# final_manual.net
KiCad netlist of a schematic drawn in EAGLE
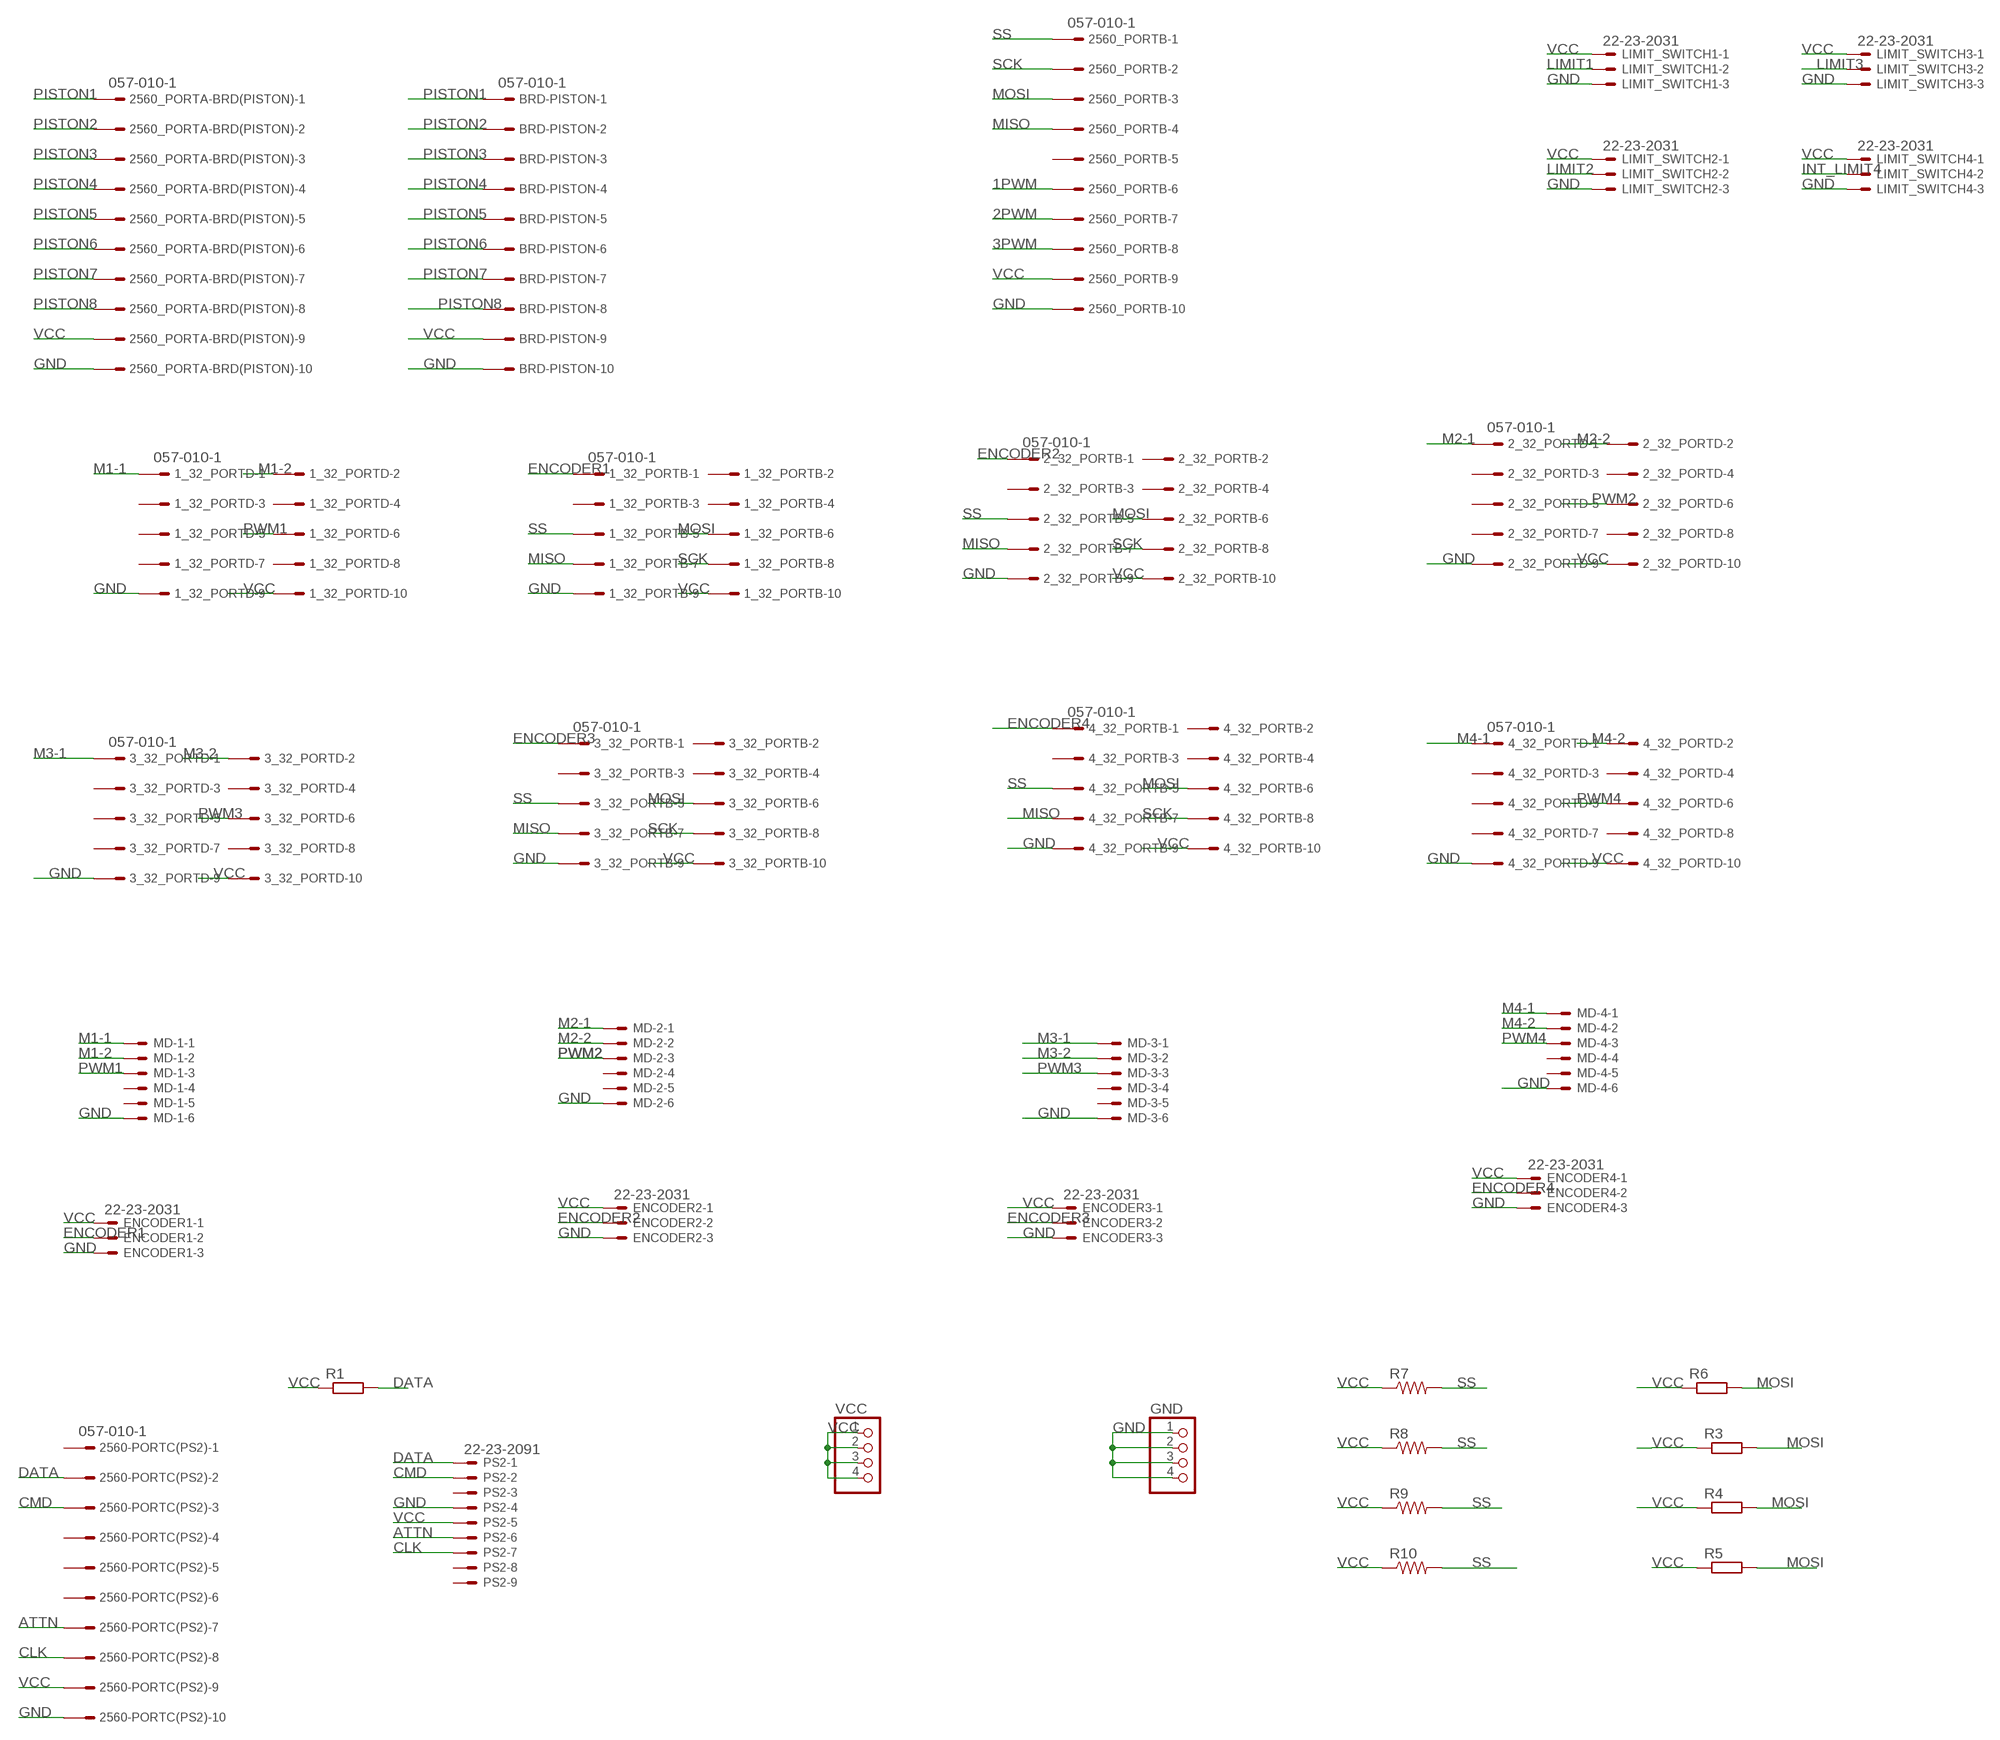
[diagram p0: schematic, sheet 1, part 1 of 2]
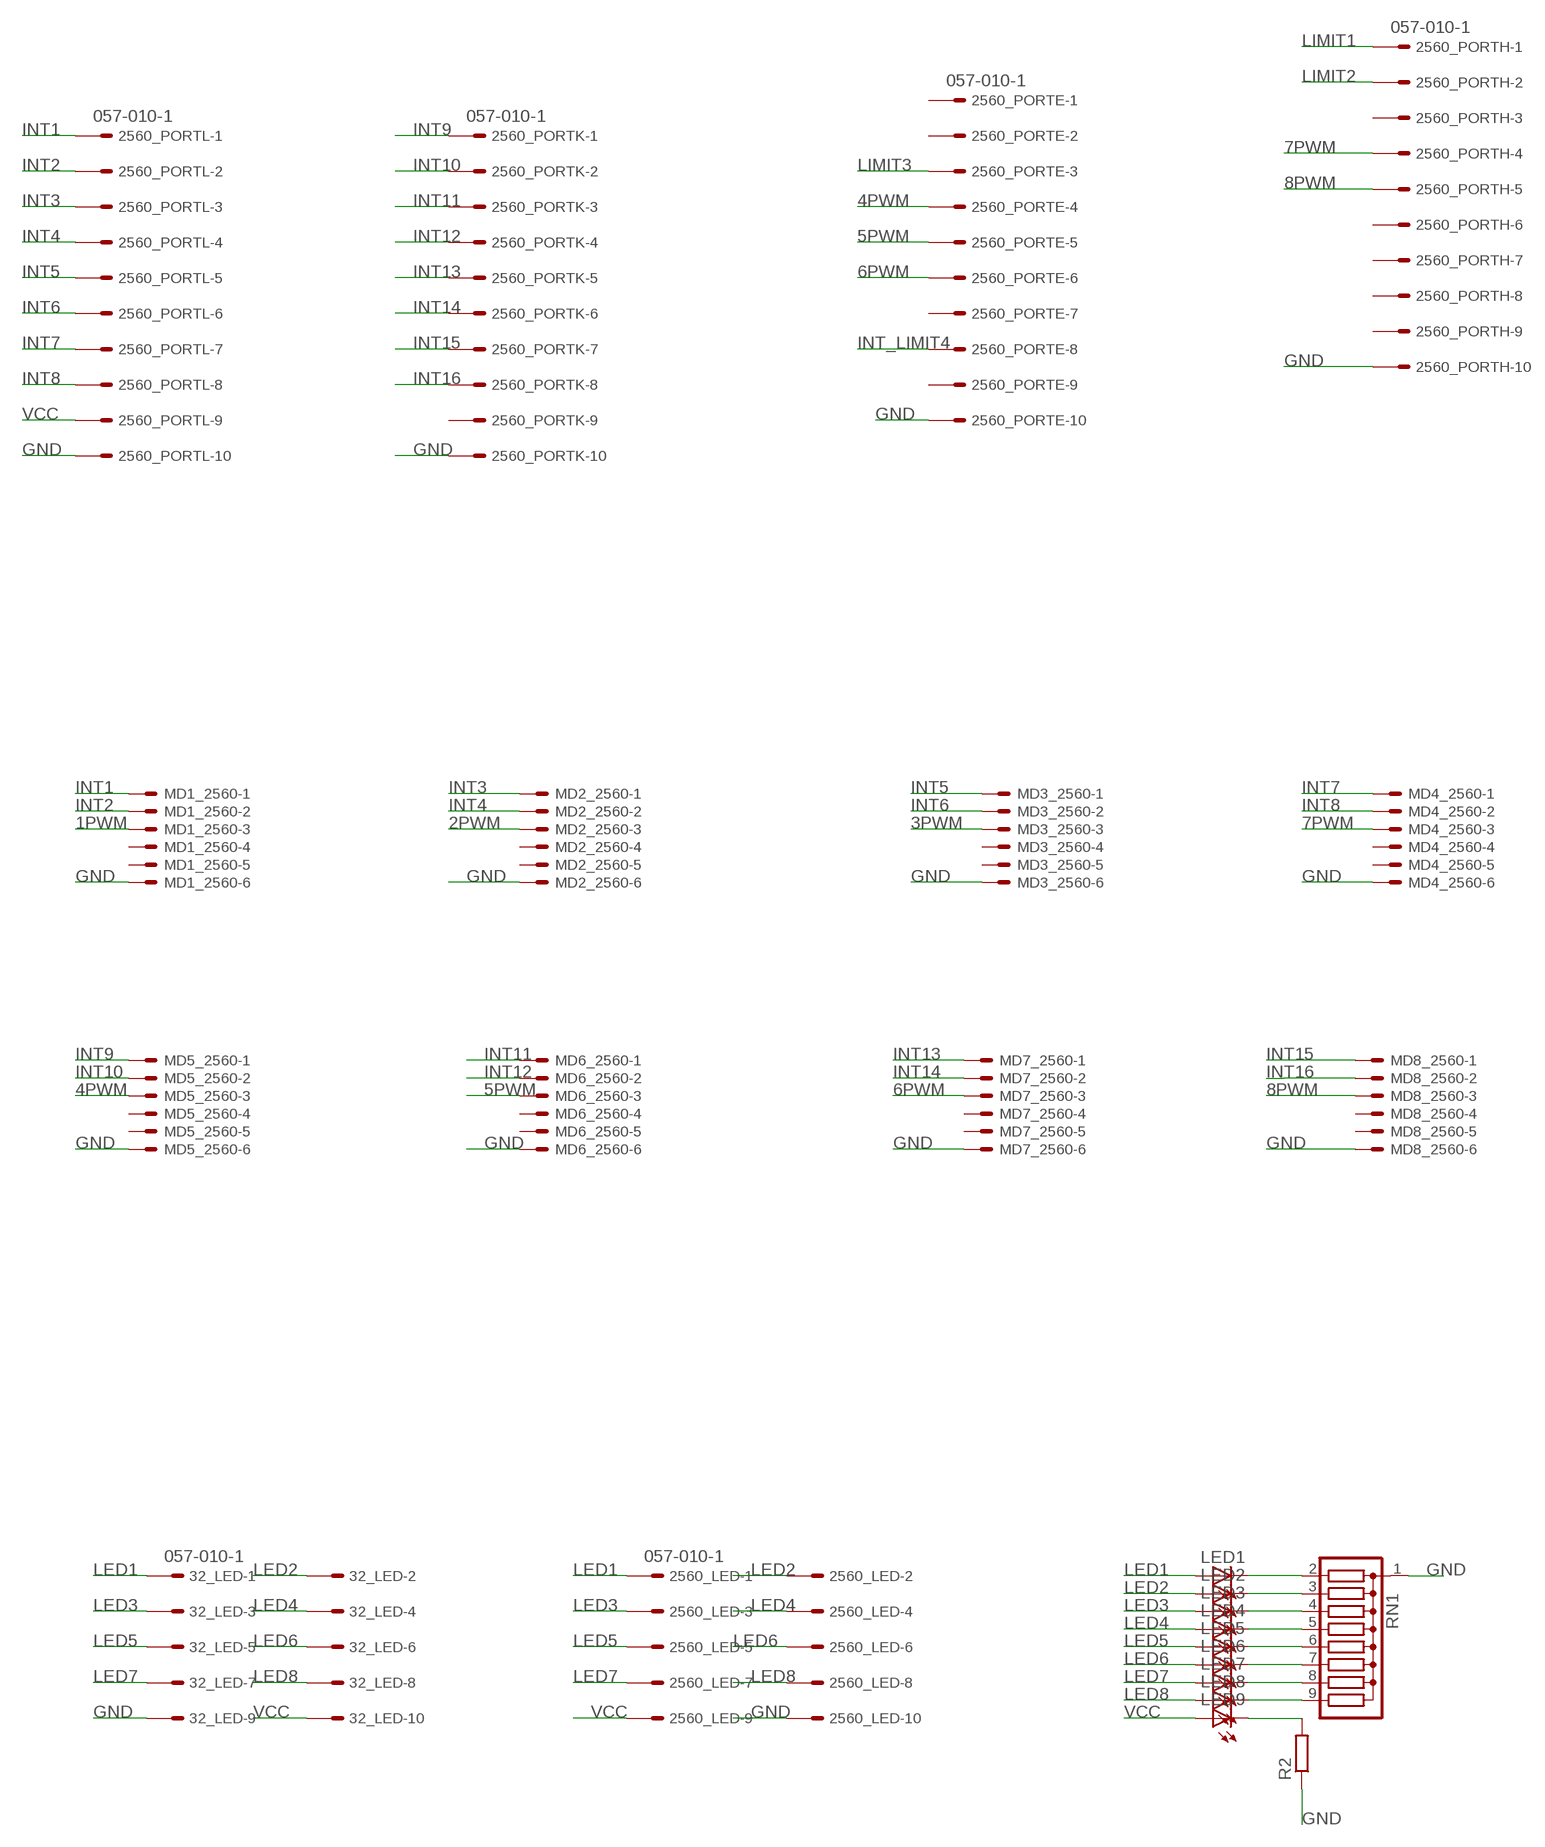
[diagram p1: schematic, sheet 1, part 2 of 2]

(export (version "E")
  (design (tool "Eeschema 10.0.6"))
  (components
    (comp (ref "1_32_PORTB")
      (value "057-010-1")
      (footprint "eagle-import:057-010-1")
      (libsource (lib "eagle-import") (part "057-010-1"))
    )
    (comp (ref "1_32_PORTD")
      (value "057-010-1")
      (footprint "eagle-import:057-010-1")
      (libsource (lib "eagle-import") (part "057-010-1"))
    )
    (comp (ref "2_32_PORTB")
      (value "057-010-1")
      (footprint "eagle-import:057-010-1")
      (libsource (lib "eagle-import") (part "057-010-1"))
    )
    (comp (ref "2_32_PORTD")
      (value "057-010-1")
      (footprint "eagle-import:057-010-1")
      (libsource (lib "eagle-import") (part "057-010-1"))
    )
    (comp (ref "3_32_PORTB")
      (value "057-010-1")
      (footprint "eagle-import:057-010-1")
      (libsource (lib "eagle-import") (part "057-010-1"))
    )
    (comp (ref "3_32_PORTD")
      (value "057-010-1")
      (footprint "eagle-import:057-010-1")
      (libsource (lib "eagle-import") (part "057-010-1"))
    )
    (comp (ref "4_32_PORTB")
      (value "057-010-1")
      (footprint "eagle-import:057-010-1")
      (libsource (lib "eagle-import") (part "057-010-1"))
    )
    (comp (ref "4_32_PORTD")
      (value "057-010-1")
      (footprint "eagle-import:057-010-1")
      (libsource (lib "eagle-import") (part "057-010-1"))
    )
    (comp (ref "32_LED")
      (value "057-010-1")
      (footprint "eagle-import:057-010-1")
      (libsource (lib "eagle-import") (part "057-010-1"))
    )
    (comp (ref "2560-PORTC(PS2)")
      (value "057-010-1")
      (footprint "eagle-import:057-010-1")
      (libsource (lib "eagle-import") (part "057-010-1"))
    )
    (comp (ref "2560_LED")
      (value "057-010-1")
      (footprint "eagle-import:057-010-1")
      (libsource (lib "eagle-import") (part "057-010-1"))
    )
    (comp (ref "2560_PORTA-BRD(PISTON)")
      (value "057-010-1")
      (footprint "eagle-import:057-010-1")
      (libsource (lib "eagle-import") (part "057-010-1"))
    )
    (comp (ref "2560_PORTB")
      (value "057-010-1")
      (footprint "eagle-import:057-010-1")
      (libsource (lib "eagle-import") (part "057-010-1"))
    )
    (comp (ref "2560_PORTE")
      (value "057-010-1")
      (footprint "eagle-import:057-010-1")
      (libsource (lib "eagle-import") (part "057-010-1"))
    )
    (comp (ref "2560_PORTH")
      (value "057-010-1")
      (footprint "eagle-import:057-010-1")
      (libsource (lib "eagle-import") (part "057-010-1"))
    )
    (comp (ref "2560_PORTK")
      (value "057-010-1")
      (footprint "eagle-import:057-010-1")
      (libsource (lib "eagle-import") (part "057-010-1"))
    )
    (comp (ref "2560_PORTL")
      (value "057-010-1")
      (footprint "eagle-import:057-010-1")
      (libsource (lib "eagle-import") (part "057-010-1"))
    )
    (comp (ref "BRD-PISTON")
      (value "057-010-1")
      (footprint "eagle-import:057-010-1")
      (libsource (lib "eagle-import") (part "057-010-1"))
    )
    (comp (ref "ENCODER1")
      (value "22-23-2031")
      (footprint "eagle-import:22-23-2031")
      (fields (field (name "MF") "MOLEX"))
      (libsource (lib "eagle-import") (part "22-23-2031"))
    )
    (comp (ref "ENCODER2")
      (value "22-23-2031")
      (footprint "eagle-import:22-23-2031")
      (fields (field (name "MF") "MOLEX"))
      (libsource (lib "eagle-import") (part "22-23-2031"))
    )
    (comp (ref "ENCODER3")
      (value "22-23-2031")
      (footprint "eagle-import:22-23-2031")
      (fields (field (name "MF") "MOLEX"))
      (libsource (lib "eagle-import") (part "22-23-2031"))
    )
    (comp (ref "ENCODER4")
      (value "22-23-2031")
      (footprint "eagle-import:22-23-2031")
      (fields (field (name "MF") "MOLEX"))
      (libsource (lib "eagle-import") (part "22-23-2031"))
    )
    (comp (ref "GND")
      (value "PINHD-1X4")
      (footprint "eagle-import:1X04")
      (libsource (lib "eagle-import") (part "PINHD-1X4"))
    )
    (comp (ref "LED1")
      (value "LED3MM")
      (footprint "eagle-import:LED3MM")
      (libsource (lib "eagle-import") (part "LED3MM"))
    )
    (comp (ref "LED2")
      (value "LED3MM")
      (footprint "eagle-import:LED3MM")
      (libsource (lib "eagle-import") (part "LED3MM"))
    )
    (comp (ref "LED3")
      (value "LED3MM")
      (footprint "eagle-import:LED3MM")
      (libsource (lib "eagle-import") (part "LED3MM"))
    )
    (comp (ref "LED4")
      (value "LED3MM")
      (footprint "eagle-import:LED3MM")
      (libsource (lib "eagle-import") (part "LED3MM"))
    )
    (comp (ref "LED5")
      (value "LED3MM")
      (footprint "eagle-import:LED3MM")
      (libsource (lib "eagle-import") (part "LED3MM"))
    )
    (comp (ref "LED6")
      (value "LED3MM")
      (footprint "eagle-import:LED3MM")
      (libsource (lib "eagle-import") (part "LED3MM"))
    )
    (comp (ref "LED7")
      (value "LED3MM")
      (footprint "eagle-import:LED3MM")
      (libsource (lib "eagle-import") (part "LED3MM"))
    )
    (comp (ref "LED8")
      (value "LED3MM")
      (footprint "eagle-import:LED3MM")
      (libsource (lib "eagle-import") (part "LED3MM"))
    )
    (comp (ref "LED9")
      (value "LED3MM")
      (footprint "eagle-import:LED3MM")
      (libsource (lib "eagle-import") (part "LED3MM"))
    )
    (comp (ref "LIMIT_SWITCH1")
      (value "22-23-2031")
      (footprint "eagle-import:22-23-2031")
      (fields (field (name "MF") "MOLEX"))
      (libsource (lib "eagle-import") (part "22-23-2031"))
    )
    (comp (ref "LIMIT_SWITCH2")
      (value "22-23-2031")
      (footprint "eagle-import:22-23-2031")
      (fields (field (name "MF") "MOLEX"))
      (libsource (lib "eagle-import") (part "22-23-2031"))
    )
    (comp (ref "LIMIT_SWITCH3")
      (value "22-23-2031")
      (footprint "eagle-import:22-23-2031")
      (fields (field (name "MF") "MOLEX"))
      (libsource (lib "eagle-import") (part "22-23-2031"))
    )
    (comp (ref "LIMIT_SWITCH4")
      (value "22-23-2031")
      (footprint "eagle-import:22-23-2031")
      (fields (field (name "MF") "MOLEX"))
      (libsource (lib "eagle-import") (part "22-23-2031"))
    )
    (comp (ref "MD-1")
      (value "22-23-2061")
      (footprint "eagle-import:22-23-2061")
      (fields (field (name "MF") "MOLEX"))
      (libsource (lib "eagle-import") (part "22-23-2061"))
    )
    (comp (ref "MD-2")
      (value "22-23-2061")
      (footprint "eagle-import:22-23-2061")
      (fields (field (name "MF") "MOLEX"))
      (libsource (lib "eagle-import") (part "22-23-2061"))
    )
    (comp (ref "MD-3")
      (value "22-23-2061")
      (footprint "eagle-import:22-23-2061")
      (fields (field (name "MF") "MOLEX"))
      (libsource (lib "eagle-import") (part "22-23-2061"))
    )
    (comp (ref "MD-4")
      (value "22-23-2061")
      (footprint "eagle-import:22-23-2061")
      (fields (field (name "MF") "MOLEX"))
      (libsource (lib "eagle-import") (part "22-23-2061"))
    )
    (comp (ref "MD1_2560")
      (value "22-23-2061")
      (footprint "eagle-import:22-23-2061")
      (fields (field (name "MF") "MOLEX"))
      (libsource (lib "eagle-import") (part "22-23-2061"))
    )
    (comp (ref "MD2_2560")
      (value "22-23-2061")
      (footprint "eagle-import:22-23-2061")
      (fields (field (name "MF") "MOLEX"))
      (libsource (lib "eagle-import") (part "22-23-2061"))
    )
    (comp (ref "MD3_2560")
      (value "22-23-2061")
      (footprint "eagle-import:22-23-2061")
      (fields (field (name "MF") "MOLEX"))
      (libsource (lib "eagle-import") (part "22-23-2061"))
    )
    (comp (ref "MD4_2560")
      (value "22-23-2061")
      (footprint "eagle-import:22-23-2061")
      (fields (field (name "MF") "MOLEX"))
      (libsource (lib "eagle-import") (part "22-23-2061"))
    )
    (comp (ref "MD5_2560")
      (value "22-23-2061")
      (footprint "eagle-import:22-23-2061")
      (fields (field (name "MF") "MOLEX"))
      (libsource (lib "eagle-import") (part "22-23-2061"))
    )
    (comp (ref "MD6_2560")
      (value "22-23-2061")
      (footprint "eagle-import:22-23-2061")
      (fields (field (name "MF") "MOLEX"))
      (libsource (lib "eagle-import") (part "22-23-2061"))
    )
    (comp (ref "MD7_2560")
      (value "22-23-2061")
      (footprint "eagle-import:22-23-2061")
      (fields (field (name "MF") "MOLEX"))
      (libsource (lib "eagle-import") (part "22-23-2061"))
    )
    (comp (ref "MD8_2560")
      (value "22-23-2061")
      (footprint "eagle-import:22-23-2061")
      (fields (field (name "MF") "MOLEX"))
      (libsource (lib "eagle-import") (part "22-23-2061"))
    )
    (comp (ref "PS2")
      (value "22-23-2091")
      (footprint "eagle-import:22-23-2091")
      (fields (field (name "MF") "MOLEX"))
      (libsource (lib "eagle-import") (part "22-23-2091"))
    )
    (comp (ref "R1")
      (value "R-EU_0204/7")
      (footprint "eagle-import:0204_7")
      (libsource (lib "eagle-import") (part "R-EU_0204/7"))
    )
    (comp (ref "R2")
      (value "R-EU_0204/7")
      (footprint "eagle-import:0204_7")
      (libsource (lib "eagle-import") (part "R-EU_0204/7"))
    )
    (comp (ref "R3")
      (value "R-EU_0204/7")
      (footprint "eagle-import:0204_7")
      (libsource (lib "eagle-import") (part "R-EU_0204/7"))
    )
    (comp (ref "R4")
      (value "R-EU_0204/7")
      (footprint "eagle-import:0204_7")
      (libsource (lib "eagle-import") (part "R-EU_0204/7"))
    )
    (comp (ref "R5")
      (value "R-EU_0204/7")
      (footprint "eagle-import:0204_7")
      (libsource (lib "eagle-import") (part "R-EU_0204/7"))
    )
    (comp (ref "R6")
      (value "R-EU_0204/7")
      (footprint "eagle-import:0204_7")
      (libsource (lib "eagle-import") (part "R-EU_0204/7"))
    )
    (comp (ref "R7")
      (value "R-US_0204/7")
      (footprint "eagle-import:0204_7")
      (libsource (lib "eagle-import") (part "R-US_0204/7"))
    )
    (comp (ref "R8")
      (value "R-US_0204/7")
      (footprint "eagle-import:0204_7")
      (libsource (lib "eagle-import") (part "R-US_0204/7"))
    )
    (comp (ref "R9")
      (value "R-US_0204/7")
      (footprint "eagle-import:0204_7")
      (libsource (lib "eagle-import") (part "R-US_0204/7"))
    )
    (comp (ref "R10")
      (value "R-US_0204/7")
      (footprint "eagle-import:0204_7")
      (libsource (lib "eagle-import") (part "R-US_0204/7"))
    )
    (comp (ref "RN1")
      (value "G08R")
      (footprint "eagle-import:SIL9")
      (libsource (lib "eagle-import") (part "G08R"))
    )
    (comp (ref "VCC")
      (value "PINHD-1X4")
      (footprint "eagle-import:1X04")
      (libsource (lib "eagle-import") (part "PINHD-1X4"))
    )
  )
  (nets
    (net (code "1") (name "/1PWM") (class "Default")
      (node (ref "2560_PORTB") (pin "6") (pinfunction "S_6") (pintype "passive"))
      (node (ref "MD1_2560") (pin "3") (pinfunction "S_3") (pintype "passive"))
    )
    (net (code "2") (name "/2PWM") (class "Default")
      (node (ref "2560_PORTB") (pin "7") (pinfunction "S_7") (pintype "passive"))
      (node (ref "MD2_2560") (pin "3") (pinfunction "S_3") (pintype "passive"))
    )
    (net (code "3") (name "/3PWM") (class "Default")
      (node (ref "2560_PORTB") (pin "8") (pinfunction "S_8") (pintype "passive"))
      (node (ref "MD3_2560") (pin "3") (pinfunction "S_3") (pintype "passive"))
    )
    (net (code "4") (name "/4PWM") (class "Default")
      (node (ref "2560_PORTE") (pin "4") (pinfunction "S_4") (pintype "passive"))
      (node (ref "MD5_2560") (pin "3") (pinfunction "S_3") (pintype "passive"))
    )
    (net (code "5") (name "/5PWM") (class "Default")
      (node (ref "2560_PORTE") (pin "5") (pinfunction "S_5") (pintype "passive"))
      (node (ref "MD6_2560") (pin "3") (pinfunction "S_3") (pintype "passive"))
    )
    (net (code "6") (name "/6PWM") (class "Default")
      (node (ref "2560_PORTE") (pin "6") (pinfunction "S_6") (pintype "passive"))
      (node (ref "MD7_2560") (pin "3") (pinfunction "S_3") (pintype "passive"))
    )
    (net (code "7") (name "/7PWM") (class "Default")
      (node (ref "2560_PORTH") (pin "4") (pinfunction "S_4") (pintype "passive"))
      (node (ref "MD4_2560") (pin "3") (pinfunction "S_3") (pintype "passive"))
    )
    (net (code "8") (name "/8PWM") (class "Default")
      (node (ref "2560_PORTH") (pin "5") (pinfunction "S_5") (pintype "passive"))
      (node (ref "MD8_2560") (pin "3") (pinfunction "S_3") (pintype "passive"))
    )
    (net (code "9") (name "/ATTN") (class "Default")
      (node (ref "2560-PORTC(PS2)") (pin "7") (pinfunction "S_7") (pintype "passive"))
      (node (ref "PS2") (pin "6") (pinfunction "S_6") (pintype "passive"))
    )
    (net (code "10") (name "/CLK") (class "Default")
      (node (ref "2560-PORTC(PS2)") (pin "8") (pinfunction "S_8") (pintype "passive"))
      (node (ref "PS2") (pin "7") (pinfunction "S_7") (pintype "passive"))
    )
    (net (code "11") (name "/CMD") (class "Default")
      (node (ref "2560-PORTC(PS2)") (pin "3") (pinfunction "S_3") (pintype "passive"))
      (node (ref "PS2") (pin "2") (pinfunction "S_2") (pintype "passive"))
    )
    (net (code "12") (name "/DATA") (class "Default")
      (node (ref "2560-PORTC(PS2)") (pin "2") (pinfunction "S_2") (pintype "passive"))
      (node (ref "PS2") (pin "1") (pinfunction "S_1") (pintype "passive"))
      (node (ref "R1") (pin "2") (pinfunction "2_2") (pintype "passive"))
    )
    (net (code "13") (name "/ENCODER1") (class "Default")
      (node (ref "1_32_PORTB") (pin "1") (pinfunction "S_1") (pintype "passive"))
      (node (ref "ENCODER1") (pin "2") (pinfunction "S_2") (pintype "passive"))
    )
    (net (code "14") (name "/ENCODER2") (class "Default")
      (node (ref "2_32_PORTB") (pin "1") (pinfunction "S_1") (pintype "passive"))
      (node (ref "ENCODER2") (pin "2") (pinfunction "S_2") (pintype "passive"))
    )
    (net (code "15") (name "/ENCODER3") (class "Default")
      (node (ref "3_32_PORTB") (pin "1") (pinfunction "S_1") (pintype "passive"))
      (node (ref "ENCODER3") (pin "2") (pinfunction "S_2") (pintype "passive"))
    )
    (net (code "16") (name "/ENCODER4") (class "Default")
      (node (ref "4_32_PORTB") (pin "1") (pinfunction "S_1") (pintype "passive"))
      (node (ref "ENCODER4") (pin "2") (pinfunction "S_2") (pintype "passive"))
    )
    (net (code "17") (name "/GND") (class "Default")
      (node (ref "1_32_PORTB") (pin "9") (pinfunction "S_9") (pintype "passive"))
      (node (ref "1_32_PORTD") (pin "9") (pinfunction "S_9") (pintype "passive"))
      (node (ref "2560-PORTC(PS2)") (pin "10") (pinfunction "S_10") (pintype "passive"))
      (node (ref "2560_LED") (pin "10") (pinfunction "S_10") (pintype "passive"))
      (node (ref "2560_PORTA-BRD(PISTON)") (pin "10") (pinfunction "S_10") (pintype "passive"))
      (node (ref "2560_PORTB") (pin "10") (pinfunction "S_10") (pintype "passive"))
      (node (ref "2560_PORTE") (pin "10") (pinfunction "S_10") (pintype "passive"))
      (node (ref "2560_PORTH") (pin "10") (pinfunction "S_10") (pintype "passive"))
      (node (ref "2560_PORTK") (pin "10") (pinfunction "S_10") (pintype "passive"))
      (node (ref "2560_PORTL") (pin "10") (pinfunction "S_10") (pintype "passive"))
      (node (ref "2_32_PORTB") (pin "9") (pinfunction "S_9") (pintype "passive"))
      (node (ref "2_32_PORTD") (pin "9") (pinfunction "S_9") (pintype "passive"))
      (node (ref "32_LED") (pin "9") (pinfunction "S_9") (pintype "passive"))
      (node (ref "3_32_PORTB") (pin "9") (pinfunction "S_9") (pintype "passive"))
      (node (ref "3_32_PORTD") (pin "9") (pinfunction "S_9") (pintype "passive"))
      (node (ref "4_32_PORTB") (pin "9") (pinfunction "S_9") (pintype "passive"))
      (node (ref "4_32_PORTD") (pin "9") (pinfunction "S_9") (pintype "passive"))
      (node (ref "BRD-PISTON") (pin "10") (pinfunction "S_10") (pintype "passive"))
      (node (ref "ENCODER1") (pin "3") (pinfunction "S_3") (pintype "passive"))
      (node (ref "ENCODER2") (pin "3") (pinfunction "S_3") (pintype "passive"))
      (node (ref "ENCODER3") (pin "3") (pinfunction "S_3") (pintype "passive"))
      (node (ref "ENCODER4") (pin "3") (pinfunction "S_3") (pintype "passive"))
      (node (ref "GND") (pin "1") (pinfunction "1_1") (pintype "passive"))
      (node (ref "GND") (pin "2") (pinfunction "2_2") (pintype "passive"))
      (node (ref "GND") (pin "3") (pinfunction "3_3") (pintype "passive"))
      (node (ref "GND") (pin "4") (pinfunction "4_4") (pintype "passive"))
      (node (ref "LIMIT_SWITCH1") (pin "3") (pinfunction "S_3") (pintype "passive"))
      (node (ref "LIMIT_SWITCH2") (pin "3") (pinfunction "S_3") (pintype "passive"))
      (node (ref "LIMIT_SWITCH3") (pin "3") (pinfunction "S_3") (pintype "passive"))
      (node (ref "LIMIT_SWITCH4") (pin "3") (pinfunction "S_3") (pintype "passive"))
      (node (ref "MD-1") (pin "6") (pinfunction "S_6") (pintype "passive"))
      (node (ref "MD-2") (pin "6") (pinfunction "S_6") (pintype "passive"))
      (node (ref "MD-3") (pin "6") (pinfunction "S_6") (pintype "passive"))
      (node (ref "MD-4") (pin "6") (pinfunction "S_6") (pintype "passive"))
      (node (ref "MD1_2560") (pin "6") (pinfunction "S_6") (pintype "passive"))
      (node (ref "MD2_2560") (pin "6") (pinfunction "S_6") (pintype "passive"))
      (node (ref "MD3_2560") (pin "6") (pinfunction "S_6") (pintype "passive"))
      (node (ref "MD4_2560") (pin "6") (pinfunction "S_6") (pintype "passive"))
      (node (ref "MD5_2560") (pin "6") (pinfunction "S_6") (pintype "passive"))
      (node (ref "MD6_2560") (pin "6") (pinfunction "S_6") (pintype "passive"))
      (node (ref "MD7_2560") (pin "6") (pinfunction "S_6") (pintype "passive"))
      (node (ref "MD8_2560") (pin "6") (pinfunction "S_6") (pintype "passive"))
      (node (ref "PS2") (pin "4") (pinfunction "S_4") (pintype "passive"))
      (node (ref "R2") (pin "1") (pinfunction "1_1") (pintype "passive"))
      (node (ref "RN1") (pin "1") (pinfunction "1_1") (pintype "passive"))
    )
    (net (code "18") (name "/INT1") (class "Default")
      (node (ref "2560_PORTL") (pin "1") (pinfunction "S_1") (pintype "passive"))
      (node (ref "MD1_2560") (pin "1") (pinfunction "S_1") (pintype "passive"))
    )
    (net (code "19") (name "/INT2") (class "Default")
      (node (ref "2560_PORTL") (pin "2") (pinfunction "S_2") (pintype "passive"))
      (node (ref "MD1_2560") (pin "2") (pinfunction "S_2") (pintype "passive"))
    )
    (net (code "20") (name "/INT3") (class "Default")
      (node (ref "2560_PORTL") (pin "3") (pinfunction "S_3") (pintype "passive"))
      (node (ref "MD2_2560") (pin "1") (pinfunction "S_1") (pintype "passive"))
    )
    (net (code "21") (name "/INT4") (class "Default")
      (node (ref "2560_PORTL") (pin "4") (pinfunction "S_4") (pintype "passive"))
      (node (ref "MD2_2560") (pin "2") (pinfunction "S_2") (pintype "passive"))
    )
    (net (code "22") (name "/INT5") (class "Default")
      (node (ref "2560_PORTL") (pin "5") (pinfunction "S_5") (pintype "passive"))
      (node (ref "MD3_2560") (pin "1") (pinfunction "S_1") (pintype "passive"))
    )
    (net (code "23") (name "/INT6") (class "Default")
      (node (ref "2560_PORTL") (pin "6") (pinfunction "S_6") (pintype "passive"))
      (node (ref "MD3_2560") (pin "2") (pinfunction "S_2") (pintype "passive"))
    )
    (net (code "24") (name "/INT7") (class "Default")
      (node (ref "2560_PORTL") (pin "7") (pinfunction "S_7") (pintype "passive"))
      (node (ref "MD4_2560") (pin "1") (pinfunction "S_1") (pintype "passive"))
    )
    (net (code "25") (name "/INT8") (class "Default")
      (node (ref "2560_PORTL") (pin "8") (pinfunction "S_8") (pintype "passive"))
      (node (ref "MD4_2560") (pin "2") (pinfunction "S_2") (pintype "passive"))
    )
    (net (code "26") (name "/INT9") (class "Default")
      (node (ref "2560_PORTK") (pin "1") (pinfunction "S_1") (pintype "passive"))
      (node (ref "MD5_2560") (pin "1") (pinfunction "S_1") (pintype "passive"))
    )
    (net (code "27") (name "/INT10") (class "Default")
      (node (ref "2560_PORTK") (pin "2") (pinfunction "S_2") (pintype "passive"))
      (node (ref "MD5_2560") (pin "2") (pinfunction "S_2") (pintype "passive"))
    )
    (net (code "28") (name "/INT11") (class "Default")
      (node (ref "2560_PORTK") (pin "3") (pinfunction "S_3") (pintype "passive"))
      (node (ref "MD6_2560") (pin "1") (pinfunction "S_1") (pintype "passive"))
    )
    (net (code "29") (name "/INT12") (class "Default")
      (node (ref "2560_PORTK") (pin "4") (pinfunction "S_4") (pintype "passive"))
      (node (ref "MD6_2560") (pin "2") (pinfunction "S_2") (pintype "passive"))
    )
    (net (code "30") (name "/INT13") (class "Default")
      (node (ref "2560_PORTK") (pin "5") (pinfunction "S_5") (pintype "passive"))
      (node (ref "MD7_2560") (pin "1") (pinfunction "S_1") (pintype "passive"))
    )
    (net (code "31") (name "/INT14") (class "Default")
      (node (ref "2560_PORTK") (pin "6") (pinfunction "S_6") (pintype "passive"))
      (node (ref "MD7_2560") (pin "2") (pinfunction "S_2") (pintype "passive"))
    )
    (net (code "32") (name "/INT15") (class "Default")
      (node (ref "2560_PORTK") (pin "7") (pinfunction "S_7") (pintype "passive"))
      (node (ref "MD8_2560") (pin "1") (pinfunction "S_1") (pintype "passive"))
    )
    (net (code "33") (name "/INT16") (class "Default")
      (node (ref "2560_PORTK") (pin "8") (pinfunction "S_8") (pintype "passive"))
      (node (ref "MD8_2560") (pin "2") (pinfunction "S_2") (pintype "passive"))
    )
    (net (code "34") (name "/INT_LIMIT4") (class "Default")
      (node (ref "2560_PORTE") (pin "8") (pinfunction "S_8") (pintype "passive"))
      (node (ref "LIMIT_SWITCH4") (pin "2") (pinfunction "S_2") (pintype "passive"))
    )
    (net (code "35") (name "/LED1") (class "Default")
      (node (ref "2560_LED") (pin "1") (pinfunction "S_1") (pintype "passive"))
      (node (ref "32_LED") (pin "1") (pinfunction "S_1") (pintype "passive"))
      (node (ref "LED1") (pin "A") (pinfunction "A_A") (pintype "passive"))
    )
    (net (code "36") (name "/LED2") (class "Default")
      (node (ref "2560_LED") (pin "2") (pinfunction "S_2") (pintype "passive"))
      (node (ref "32_LED") (pin "2") (pinfunction "S_2") (pintype "passive"))
      (node (ref "LED2") (pin "A") (pinfunction "A_A") (pintype "passive"))
    )
    (net (code "37") (name "/LED3") (class "Default")
      (node (ref "2560_LED") (pin "3") (pinfunction "S_3") (pintype "passive"))
      (node (ref "32_LED") (pin "3") (pinfunction "S_3") (pintype "passive"))
      (node (ref "LED3") (pin "A") (pinfunction "A_A") (pintype "passive"))
    )
    (net (code "38") (name "/LED4") (class "Default")
      (node (ref "2560_LED") (pin "4") (pinfunction "S_4") (pintype "passive"))
      (node (ref "32_LED") (pin "4") (pinfunction "S_4") (pintype "passive"))
      (node (ref "LED4") (pin "A") (pinfunction "A_A") (pintype "passive"))
    )
    (net (code "39") (name "/LED5") (class "Default")
      (node (ref "2560_LED") (pin "5") (pinfunction "S_5") (pintype "passive"))
      (node (ref "32_LED") (pin "5") (pinfunction "S_5") (pintype "passive"))
      (node (ref "LED5") (pin "A") (pinfunction "A_A") (pintype "passive"))
    )
    (net (code "40") (name "/LED6") (class "Default")
      (node (ref "2560_LED") (pin "6") (pinfunction "S_6") (pintype "passive"))
      (node (ref "32_LED") (pin "6") (pinfunction "S_6") (pintype "passive"))
      (node (ref "LED6") (pin "A") (pinfunction "A_A") (pintype "passive"))
    )
    (net (code "41") (name "/LED7") (class "Default")
      (node (ref "2560_LED") (pin "7") (pinfunction "S_7") (pintype "passive"))
      (node (ref "32_LED") (pin "7") (pinfunction "S_7") (pintype "passive"))
      (node (ref "LED7") (pin "A") (pinfunction "A_A") (pintype "passive"))
    )
    (net (code "42") (name "/LED8") (class "Default")
      (node (ref "2560_LED") (pin "8") (pinfunction "S_8") (pintype "passive"))
      (node (ref "32_LED") (pin "8") (pinfunction "S_8") (pintype "passive"))
      (node (ref "LED8") (pin "A") (pinfunction "A_A") (pintype "passive"))
    )
    (net (code "43") (name "/LIMIT1") (class "Default")
      (node (ref "2560_PORTH") (pin "1") (pinfunction "S_1") (pintype "passive"))
      (node (ref "LIMIT_SWITCH1") (pin "2") (pinfunction "S_2") (pintype "passive"))
    )
    (net (code "44") (name "/LIMIT2") (class "Default")
      (node (ref "2560_PORTH") (pin "2") (pinfunction "S_2") (pintype "passive"))
      (node (ref "LIMIT_SWITCH2") (pin "2") (pinfunction "S_2") (pintype "passive"))
    )
    (net (code "45") (name "/LIMIT3") (class "Default")
      (node (ref "2560_PORTE") (pin "3") (pinfunction "S_3") (pintype "passive"))
      (node (ref "LIMIT_SWITCH3") (pin "2") (pinfunction "S_2") (pintype "passive"))
    )
    (net (code "46") (name "/M1-1") (class "Default")
      (node (ref "1_32_PORTD") (pin "1") (pinfunction "S_1") (pintype "passive"))
      (node (ref "MD-1") (pin "1") (pinfunction "S_1") (pintype "passive"))
    )
    (net (code "47") (name "/M1-2") (class "Default")
      (node (ref "1_32_PORTD") (pin "2") (pinfunction "S_2") (pintype "passive"))
      (node (ref "MD-1") (pin "2") (pinfunction "S_2") (pintype "passive"))
    )
    (net (code "48") (name "/M2-1") (class "Default")
      (node (ref "2_32_PORTD") (pin "1") (pinfunction "S_1") (pintype "passive"))
      (node (ref "MD-2") (pin "1") (pinfunction "S_1") (pintype "passive"))
    )
    (net (code "49") (name "/M2-2") (class "Default")
      (node (ref "2_32_PORTD") (pin "2") (pinfunction "S_2") (pintype "passive"))
      (node (ref "MD-2") (pin "2") (pinfunction "S_2") (pintype "passive"))
    )
    (net (code "50") (name "/M3-1") (class "Default")
      (node (ref "3_32_PORTD") (pin "1") (pinfunction "S_1") (pintype "passive"))
      (node (ref "MD-3") (pin "1") (pinfunction "S_1") (pintype "passive"))
    )
    (net (code "51") (name "/M3-2") (class "Default")
      (node (ref "3_32_PORTD") (pin "2") (pinfunction "S_2") (pintype "passive"))
      (node (ref "MD-3") (pin "2") (pinfunction "S_2") (pintype "passive"))
    )
    (net (code "52") (name "/M4-1") (class "Default")
      (node (ref "4_32_PORTD") (pin "1") (pinfunction "S_1") (pintype "passive"))
      (node (ref "MD-4") (pin "1") (pinfunction "S_1") (pintype "passive"))
    )
    (net (code "53") (name "/M4-2") (class "Default")
      (node (ref "4_32_PORTD") (pin "2") (pinfunction "S_2") (pintype "passive"))
      (node (ref "MD-4") (pin "2") (pinfunction "S_2") (pintype "passive"))
    )
    (net (code "54") (name "/MISO") (class "Default")
      (node (ref "1_32_PORTB") (pin "7") (pinfunction "S_7") (pintype "passive"))
      (node (ref "2560_PORTB") (pin "4") (pinfunction "S_4") (pintype "passive"))
      (node (ref "2_32_PORTB") (pin "7") (pinfunction "S_7") (pintype "passive"))
      (node (ref "3_32_PORTB") (pin "7") (pinfunction "S_7") (pintype "passive"))
      (node (ref "4_32_PORTB") (pin "7") (pinfunction "S_7") (pintype "passive"))
    )
    (net (code "55") (name "/MOSI") (class "Default")
      (node (ref "1_32_PORTB") (pin "6") (pinfunction "S_6") (pintype "passive"))
      (node (ref "2560_PORTB") (pin "3") (pinfunction "S_3") (pintype "passive"))
      (node (ref "2_32_PORTB") (pin "6") (pinfunction "S_6") (pintype "passive"))
      (node (ref "3_32_PORTB") (pin "6") (pinfunction "S_6") (pintype "passive"))
      (node (ref "4_32_PORTB") (pin "6") (pinfunction "S_6") (pintype "passive"))
      (node (ref "R3") (pin "2") (pinfunction "2_2") (pintype "passive"))
      (node (ref "R4") (pin "2") (pinfunction "2_2") (pintype "passive"))
      (node (ref "R5") (pin "2") (pinfunction "2_2") (pintype "passive"))
      (node (ref "R6") (pin "2") (pinfunction "2_2") (pintype "passive"))
    )
    (net (code "56") (name "/PISTON1") (class "Default")
      (node (ref "2560_PORTA-BRD(PISTON)") (pin "1") (pinfunction "S_1") (pintype "passive"))
      (node (ref "BRD-PISTON") (pin "1") (pinfunction "S_1") (pintype "passive"))
    )
    (net (code "57") (name "/PISTON2") (class "Default")
      (node (ref "2560_PORTA-BRD(PISTON)") (pin "2") (pinfunction "S_2") (pintype "passive"))
      (node (ref "BRD-PISTON") (pin "2") (pinfunction "S_2") (pintype "passive"))
    )
    (net (code "58") (name "/PISTON3") (class "Default")
      (node (ref "2560_PORTA-BRD(PISTON)") (pin "3") (pinfunction "S_3") (pintype "passive"))
      (node (ref "BRD-PISTON") (pin "3") (pinfunction "S_3") (pintype "passive"))
    )
    (net (code "59") (name "/PISTON4") (class "Default")
      (node (ref "2560_PORTA-BRD(PISTON)") (pin "4") (pinfunction "S_4") (pintype "passive"))
      (node (ref "BRD-PISTON") (pin "4") (pinfunction "S_4") (pintype "passive"))
    )
    (net (code "60") (name "/PISTON5") (class "Default")
      (node (ref "2560_PORTA-BRD(PISTON)") (pin "5") (pinfunction "S_5") (pintype "passive"))
      (node (ref "BRD-PISTON") (pin "5") (pinfunction "S_5") (pintype "passive"))
    )
    (net (code "61") (name "/PISTON6") (class "Default")
      (node (ref "2560_PORTA-BRD(PISTON)") (pin "6") (pinfunction "S_6") (pintype "passive"))
      (node (ref "BRD-PISTON") (pin "6") (pinfunction "S_6") (pintype "passive"))
    )
    (net (code "62") (name "/PISTON7") (class "Default")
      (node (ref "2560_PORTA-BRD(PISTON)") (pin "7") (pinfunction "S_7") (pintype "passive"))
      (node (ref "BRD-PISTON") (pin "7") (pinfunction "S_7") (pintype "passive"))
    )
    (net (code "63") (name "/PISTON8") (class "Default")
      (node (ref "2560_PORTA-BRD(PISTON)") (pin "8") (pinfunction "S_8") (pintype "passive"))
      (node (ref "BRD-PISTON") (pin "8") (pinfunction "S_8") (pintype "passive"))
    )
    (net (code "64") (name "/PWM1") (class "Default")
      (node (ref "1_32_PORTD") (pin "6") (pinfunction "S_6") (pintype "passive"))
      (node (ref "MD-1") (pin "3") (pinfunction "S_3") (pintype "passive"))
    )
    (net (code "65") (name "/PWM2") (class "Default")
      (node (ref "2_32_PORTD") (pin "6") (pinfunction "S_6") (pintype "passive"))
      (node (ref "MD-2") (pin "3") (pinfunction "S_3") (pintype "passive"))
    )
    (net (code "66") (name "/PWM3") (class "Default")
      (node (ref "3_32_PORTD") (pin "6") (pinfunction "S_6") (pintype "passive"))
      (node (ref "MD-3") (pin "3") (pinfunction "S_3") (pintype "passive"))
    )
    (net (code "67") (name "/PWM4") (class "Default")
      (node (ref "4_32_PORTD") (pin "6") (pinfunction "S_6") (pintype "passive"))
      (node (ref "MD-4") (pin "3") (pinfunction "S_3") (pintype "passive"))
    )
    (net (code "68") (name "/SCK") (class "Default")
      (node (ref "1_32_PORTB") (pin "8") (pinfunction "S_8") (pintype "passive"))
      (node (ref "2560_PORTB") (pin "2") (pinfunction "S_2") (pintype "passive"))
      (node (ref "2_32_PORTB") (pin "8") (pinfunction "S_8") (pintype "passive"))
      (node (ref "3_32_PORTB") (pin "8") (pinfunction "S_8") (pintype "passive"))
      (node (ref "4_32_PORTB") (pin "8") (pinfunction "S_8") (pintype "passive"))
    )
    (net (code "69") (name "/SS") (class "Default")
      (node (ref "1_32_PORTB") (pin "5") (pinfunction "S_5") (pintype "passive"))
      (node (ref "2560_PORTB") (pin "1") (pinfunction "S_1") (pintype "passive"))
      (node (ref "2_32_PORTB") (pin "5") (pinfunction "S_5") (pintype "passive"))
      (node (ref "3_32_PORTB") (pin "5") (pinfunction "S_5") (pintype "passive"))
      (node (ref "4_32_PORTB") (pin "5") (pinfunction "S_5") (pintype "passive"))
      (node (ref "R10") (pin "2") (pinfunction "2_2") (pintype "passive"))
      (node (ref "R7") (pin "2") (pinfunction "2_2") (pintype "passive"))
      (node (ref "R8") (pin "2") (pinfunction "2_2") (pintype "passive"))
      (node (ref "R9") (pin "2") (pinfunction "2_2") (pintype "passive"))
    )
    (net (code "70") (name "/VCC") (class "Default")
      (node (ref "1_32_PORTB") (pin "10") (pinfunction "S_10") (pintype "passive"))
      (node (ref "1_32_PORTD") (pin "10") (pinfunction "S_10") (pintype "passive"))
      (node (ref "2560-PORTC(PS2)") (pin "9") (pinfunction "S_9") (pintype "passive"))
      (node (ref "2560_LED") (pin "9") (pinfunction "S_9") (pintype "passive"))
      (node (ref "2560_PORTA-BRD(PISTON)") (pin "9") (pinfunction "S_9") (pintype "passive"))
      (node (ref "2560_PORTB") (pin "9") (pinfunction "S_9") (pintype "passive"))
      (node (ref "2560_PORTL") (pin "9") (pinfunction "S_9") (pintype "passive"))
      (node (ref "2_32_PORTB") (pin "10") (pinfunction "S_10") (pintype "passive"))
      (node (ref "2_32_PORTD") (pin "10") (pinfunction "S_10") (pintype "passive"))
      (node (ref "32_LED") (pin "10") (pinfunction "S_10") (pintype "passive"))
      (node (ref "3_32_PORTB") (pin "10") (pinfunction "S_10") (pintype "passive"))
      (node (ref "3_32_PORTD") (pin "10") (pinfunction "S_10") (pintype "passive"))
      (node (ref "4_32_PORTB") (pin "10") (pinfunction "S_10") (pintype "passive"))
      (node (ref "4_32_PORTD") (pin "10") (pinfunction "S_10") (pintype "passive"))
      (node (ref "BRD-PISTON") (pin "9") (pinfunction "S_9") (pintype "passive"))
      (node (ref "ENCODER1") (pin "1") (pinfunction "S_1") (pintype "passive"))
      (node (ref "ENCODER2") (pin "1") (pinfunction "S_1") (pintype "passive"))
      (node (ref "ENCODER3") (pin "1") (pinfunction "S_1") (pintype "passive"))
      (node (ref "ENCODER4") (pin "1") (pinfunction "S_1") (pintype "passive"))
      (node (ref "LED9") (pin "A") (pinfunction "A_A") (pintype "passive"))
      (node (ref "LIMIT_SWITCH1") (pin "1") (pinfunction "S_1") (pintype "passive"))
      (node (ref "LIMIT_SWITCH2") (pin "1") (pinfunction "S_1") (pintype "passive"))
      (node (ref "LIMIT_SWITCH3") (pin "1") (pinfunction "S_1") (pintype "passive"))
      (node (ref "LIMIT_SWITCH4") (pin "1") (pinfunction "S_1") (pintype "passive"))
      (node (ref "PS2") (pin "5") (pinfunction "S_5") (pintype "passive"))
      (node (ref "R1") (pin "1") (pinfunction "1_1") (pintype "passive"))
      (node (ref "R10") (pin "1") (pinfunction "1_1") (pintype "passive"))
      (node (ref "R3") (pin "1") (pinfunction "1_1") (pintype "passive"))
      (node (ref "R4") (pin "1") (pinfunction "1_1") (pintype "passive"))
      (node (ref "R5") (pin "1") (pinfunction "1_1") (pintype "passive"))
      (node (ref "R6") (pin "1") (pinfunction "1_1") (pintype "passive"))
      (node (ref "R7") (pin "1") (pinfunction "1_1") (pintype "passive"))
      (node (ref "R8") (pin "1") (pinfunction "1_1") (pintype "passive"))
      (node (ref "R9") (pin "1") (pinfunction "1_1") (pintype "passive"))
      (node (ref "VCC") (pin "1") (pinfunction "1_1") (pintype "passive"))
      (node (ref "VCC") (pin "2") (pinfunction "2_2") (pintype "passive"))
      (node (ref "VCC") (pin "3") (pinfunction "3_3") (pintype "passive"))
      (node (ref "VCC") (pin "4") (pinfunction "4_4") (pintype "passive"))
    )
    (net (code "71") (name "Net-(LED1-C)") (class "Default")
      (node (ref "LED1") (pin "K") (pinfunction "C_K") (pintype "passive"))
      (node (ref "RN1") (pin "2") (pinfunction "2_2") (pintype "passive"))
    )
    (net (code "72") (name "Net-(LED2-C)") (class "Default")
      (node (ref "LED2") (pin "K") (pinfunction "C_K") (pintype "passive"))
      (node (ref "RN1") (pin "3") (pinfunction "3_3") (pintype "passive"))
    )
    (net (code "73") (name "Net-(LED3-C)") (class "Default")
      (node (ref "LED3") (pin "K") (pinfunction "C_K") (pintype "passive"))
      (node (ref "RN1") (pin "4") (pinfunction "4_4") (pintype "passive"))
    )
    (net (code "74") (name "Net-(LED4-C)") (class "Default")
      (node (ref "LED4") (pin "K") (pinfunction "C_K") (pintype "passive"))
      (node (ref "RN1") (pin "5") (pinfunction "5_5") (pintype "passive"))
    )
    (net (code "75") (name "Net-(LED5-C)") (class "Default")
      (node (ref "LED5") (pin "K") (pinfunction "C_K") (pintype "passive"))
      (node (ref "RN1") (pin "6") (pinfunction "6_6") (pintype "passive"))
    )
    (net (code "76") (name "Net-(LED6-C)") (class "Default")
      (node (ref "LED6") (pin "K") (pinfunction "C_K") (pintype "passive"))
      (node (ref "RN1") (pin "7") (pinfunction "7_7") (pintype "passive"))
    )
    (net (code "77") (name "Net-(LED7-C)") (class "Default")
      (node (ref "LED7") (pin "K") (pinfunction "C_K") (pintype "passive"))
      (node (ref "RN1") (pin "8") (pinfunction "8_8") (pintype "passive"))
    )
    (net (code "78") (name "Net-(LED8-C)") (class "Default")
      (node (ref "LED8") (pin "K") (pinfunction "C_K") (pintype "passive"))
      (node (ref "RN1") (pin "9") (pinfunction "9_9") (pintype "passive"))
    )
    (net (code "79") (name "Net-(LED9-C)") (class "Default")
      (node (ref "LED9") (pin "K") (pinfunction "C_K") (pintype "passive"))
      (node (ref "R2") (pin "2") (pinfunction "2_2") (pintype "passive"))
    )
    (net (code "80") (name "unconnected-(1_32_PORTBC-S-Pad2)") (class "Default")
      (node (ref "1_32_PORTB") (pin "2") (pinfunction "S_2") (pintype "passive"))
    )
    (net (code "81") (name "unconnected-(1_32_PORTBD-S-Pad3)") (class "Default")
      (node (ref "1_32_PORTB") (pin "3") (pinfunction "S_3") (pintype "passive"))
    )
    (net (code "82") (name "unconnected-(1_32_PORTBE-S-Pad4)") (class "Default")
      (node (ref "1_32_PORTB") (pin "4") (pinfunction "S_4") (pintype "passive"))
    )
    (net (code "83") (name "unconnected-(1_32_PORTDD-S-Pad3)") (class "Default")
      (node (ref "1_32_PORTD") (pin "3") (pinfunction "S_3") (pintype "passive"))
    )
    (net (code "84") (name "unconnected-(1_32_PORTDE-S-Pad4)") (class "Default")
      (node (ref "1_32_PORTD") (pin "4") (pinfunction "S_4") (pintype "passive"))
    )
    (net (code "85") (name "unconnected-(1_32_PORTDF-S-Pad5)") (class "Default")
      (node (ref "1_32_PORTD") (pin "5") (pinfunction "S_5") (pintype "passive"))
    )
    (net (code "86") (name "unconnected-(1_32_PORTDH-S-Pad7)") (class "Default")
      (node (ref "1_32_PORTD") (pin "7") (pinfunction "S_7") (pintype "passive"))
    )
    (net (code "87") (name "unconnected-(1_32_PORTDI-S-Pad8)") (class "Default")
      (node (ref "1_32_PORTD") (pin "8") (pinfunction "S_8") (pintype "passive"))
    )
    (net (code "88") (name "unconnected-(2_32_PORTBC-S-Pad2)") (class "Default")
      (node (ref "2_32_PORTB") (pin "2") (pinfunction "S_2") (pintype "passive"))
    )
    (net (code "89") (name "unconnected-(2_32_PORTBD-S-Pad3)") (class "Default")
      (node (ref "2_32_PORTB") (pin "3") (pinfunction "S_3") (pintype "passive"))
    )
    (net (code "90") (name "unconnected-(2_32_PORTBE-S-Pad4)") (class "Default")
      (node (ref "2_32_PORTB") (pin "4") (pinfunction "S_4") (pintype "passive"))
    )
    (net (code "91") (name "unconnected-(2_32_PORTDD-S-Pad3)") (class "Default")
      (node (ref "2_32_PORTD") (pin "3") (pinfunction "S_3") (pintype "passive"))
    )
    (net (code "92") (name "unconnected-(2_32_PORTDE-S-Pad4)") (class "Default")
      (node (ref "2_32_PORTD") (pin "4") (pinfunction "S_4") (pintype "passive"))
    )
    (net (code "93") (name "unconnected-(2_32_PORTDF-S-Pad5)") (class "Default")
      (node (ref "2_32_PORTD") (pin "5") (pinfunction "S_5") (pintype "passive"))
    )
    (net (code "94") (name "unconnected-(2_32_PORTDH-S-Pad7)") (class "Default")
      (node (ref "2_32_PORTD") (pin "7") (pinfunction "S_7") (pintype "passive"))
    )
    (net (code "95") (name "unconnected-(2_32_PORTDI-S-Pad8)") (class "Default")
      (node (ref "2_32_PORTD") (pin "8") (pinfunction "S_8") (pintype "passive"))
    )
    (net (code "96") (name "unconnected-(3_32_PORTBC-S-Pad2)") (class "Default")
      (node (ref "3_32_PORTB") (pin "2") (pinfunction "S_2") (pintype "passive"))
    )
    (net (code "97") (name "unconnected-(3_32_PORTBD-S-Pad3)") (class "Default")
      (node (ref "3_32_PORTB") (pin "3") (pinfunction "S_3") (pintype "passive"))
    )
    (net (code "98") (name "unconnected-(3_32_PORTBE-S-Pad4)") (class "Default")
      (node (ref "3_32_PORTB") (pin "4") (pinfunction "S_4") (pintype "passive"))
    )
    (net (code "99") (name "unconnected-(3_32_PORTDD-S-Pad3)") (class "Default")
      (node (ref "3_32_PORTD") (pin "3") (pinfunction "S_3") (pintype "passive"))
    )
    (net (code "100") (name "unconnected-(3_32_PORTDE-S-Pad4)") (class "Default")
      (node (ref "3_32_PORTD") (pin "4") (pinfunction "S_4") (pintype "passive"))
    )
    (net (code "101") (name "unconnected-(3_32_PORTDF-S-Pad5)") (class "Default")
      (node (ref "3_32_PORTD") (pin "5") (pinfunction "S_5") (pintype "passive"))
    )
    (net (code "102") (name "unconnected-(3_32_PORTDH-S-Pad7)") (class "Default")
      (node (ref "3_32_PORTD") (pin "7") (pinfunction "S_7") (pintype "passive"))
    )
    (net (code "103") (name "unconnected-(3_32_PORTDI-S-Pad8)") (class "Default")
      (node (ref "3_32_PORTD") (pin "8") (pinfunction "S_8") (pintype "passive"))
    )
    (net (code "104") (name "unconnected-(4_32_PORTBC-S-Pad2)") (class "Default")
      (node (ref "4_32_PORTB") (pin "2") (pinfunction "S_2") (pintype "passive"))
    )
    (net (code "105") (name "unconnected-(4_32_PORTBD-S-Pad3)") (class "Default")
      (node (ref "4_32_PORTB") (pin "3") (pinfunction "S_3") (pintype "passive"))
    )
    (net (code "106") (name "unconnected-(4_32_PORTBE-S-Pad4)") (class "Default")
      (node (ref "4_32_PORTB") (pin "4") (pinfunction "S_4") (pintype "passive"))
    )
    (net (code "107") (name "unconnected-(4_32_PORTDD-S-Pad3)") (class "Default")
      (node (ref "4_32_PORTD") (pin "3") (pinfunction "S_3") (pintype "passive"))
    )
    (net (code "108") (name "unconnected-(4_32_PORTDE-S-Pad4)") (class "Default")
      (node (ref "4_32_PORTD") (pin "4") (pinfunction "S_4") (pintype "passive"))
    )
    (net (code "109") (name "unconnected-(4_32_PORTDF-S-Pad5)") (class "Default")
      (node (ref "4_32_PORTD") (pin "5") (pinfunction "S_5") (pintype "passive"))
    )
    (net (code "110") (name "unconnected-(4_32_PORTDH-S-Pad7)") (class "Default")
      (node (ref "4_32_PORTD") (pin "7") (pinfunction "S_7") (pintype "passive"))
    )
    (net (code "111") (name "unconnected-(4_32_PORTDI-S-Pad8)") (class "Default")
      (node (ref "4_32_PORTD") (pin "8") (pinfunction "S_8") (pintype "passive"))
    )
    (net (code "112") (name "unconnected-(2560-PORTC(PS2)A-S-Pad1)") (class "Default")
      (node (ref "2560-PORTC(PS2)") (pin "1") (pinfunction "S_1") (pintype "passive"))
    )
    (net (code "113") (name "unconnected-(2560-PORTC(PS2)E-S-Pad4)") (class "Default")
      (node (ref "2560-PORTC(PS2)") (pin "4") (pinfunction "S_4") (pintype "passive"))
    )
    (net (code "114") (name "unconnected-(2560-PORTC(PS2)F-S-Pad5)") (class "Default")
      (node (ref "2560-PORTC(PS2)") (pin "5") (pinfunction "S_5") (pintype "passive"))
    )
    (net (code "115") (name "unconnected-(2560-PORTC(PS2)G-S-Pad6)") (class "Default")
      (node (ref "2560-PORTC(PS2)") (pin "6") (pinfunction "S_6") (pintype "passive"))
    )
    (net (code "116") (name "unconnected-(2560_PORTBF-S-Pad5)") (class "Default")
      (node (ref "2560_PORTB") (pin "5") (pinfunction "S_5") (pintype "passive"))
    )
    (net (code "117") (name "unconnected-(2560_PORTEA-S-Pad1)") (class "Default")
      (node (ref "2560_PORTE") (pin "1") (pinfunction "S_1") (pintype "passive"))
    )
    (net (code "118") (name "unconnected-(2560_PORTEC-S-Pad2)") (class "Default")
      (node (ref "2560_PORTE") (pin "2") (pinfunction "S_2") (pintype "passive"))
    )
    (net (code "119") (name "unconnected-(2560_PORTEH-S-Pad7)") (class "Default")
      (node (ref "2560_PORTE") (pin "7") (pinfunction "S_7") (pintype "passive"))
    )
    (net (code "120") (name "unconnected-(2560_PORTEJ-S-Pad9)") (class "Default")
      (node (ref "2560_PORTE") (pin "9") (pinfunction "S_9") (pintype "passive"))
    )
    (net (code "121") (name "unconnected-(2560_PORTHD-S-Pad3)") (class "Default")
      (node (ref "2560_PORTH") (pin "3") (pinfunction "S_3") (pintype "passive"))
    )
    (net (code "122") (name "unconnected-(2560_PORTHG-S-Pad6)") (class "Default")
      (node (ref "2560_PORTH") (pin "6") (pinfunction "S_6") (pintype "passive"))
    )
    (net (code "123") (name "unconnected-(2560_PORTHH-S-Pad7)") (class "Default")
      (node (ref "2560_PORTH") (pin "7") (pinfunction "S_7") (pintype "passive"))
    )
    (net (code "124") (name "unconnected-(2560_PORTHI-S-Pad8)") (class "Default")
      (node (ref "2560_PORTH") (pin "8") (pinfunction "S_8") (pintype "passive"))
    )
    (net (code "125") (name "unconnected-(2560_PORTHJ-S-Pad9)") (class "Default")
      (node (ref "2560_PORTH") (pin "9") (pinfunction "S_9") (pintype "passive"))
    )
    (net (code "126") (name "unconnected-(2560_PORTKJ-S-Pad9)") (class "Default")
      (node (ref "2560_PORTK") (pin "9") (pinfunction "S_9") (pintype "passive"))
    )
    (net (code "127") (name "unconnected-(MD-1D-S-Pad4)") (class "Default")
      (node (ref "MD-1") (pin "4") (pinfunction "S_4") (pintype "passive"))
    )
    (net (code "128") (name "unconnected-(MD-1E-S-Pad5)") (class "Default")
      (node (ref "MD-1") (pin "5") (pinfunction "S_5") (pintype "passive"))
    )
    (net (code "129") (name "unconnected-(MD-2D-S-Pad4)") (class "Default")
      (node (ref "MD-2") (pin "4") (pinfunction "S_4") (pintype "passive"))
    )
    (net (code "130") (name "unconnected-(MD-2E-S-Pad5)") (class "Default")
      (node (ref "MD-2") (pin "5") (pinfunction "S_5") (pintype "passive"))
    )
    (net (code "131") (name "unconnected-(MD-3D-S-Pad4)") (class "Default")
      (node (ref "MD-3") (pin "4") (pinfunction "S_4") (pintype "passive"))
    )
    (net (code "132") (name "unconnected-(MD-3E-S-Pad5)") (class "Default")
      (node (ref "MD-3") (pin "5") (pinfunction "S_5") (pintype "passive"))
    )
    (net (code "133") (name "unconnected-(MD-4D-S-Pad4)") (class "Default")
      (node (ref "MD-4") (pin "4") (pinfunction "S_4") (pintype "passive"))
    )
    (net (code "134") (name "unconnected-(MD-4E-S-Pad5)") (class "Default")
      (node (ref "MD-4") (pin "5") (pinfunction "S_5") (pintype "passive"))
    )
    (net (code "135") (name "unconnected-(MD1_2560D-S-Pad4)") (class "Default")
      (node (ref "MD1_2560") (pin "4") (pinfunction "S_4") (pintype "passive"))
    )
    (net (code "136") (name "unconnected-(MD1_2560E-S-Pad5)") (class "Default")
      (node (ref "MD1_2560") (pin "5") (pinfunction "S_5") (pintype "passive"))
    )
    (net (code "137") (name "unconnected-(MD2_2560D-S-Pad4)") (class "Default")
      (node (ref "MD2_2560") (pin "4") (pinfunction "S_4") (pintype "passive"))
    )
    (net (code "138") (name "unconnected-(MD2_2560E-S-Pad5)") (class "Default")
      (node (ref "MD2_2560") (pin "5") (pinfunction "S_5") (pintype "passive"))
    )
    (net (code "139") (name "unconnected-(MD3_2560D-S-Pad4)") (class "Default")
      (node (ref "MD3_2560") (pin "4") (pinfunction "S_4") (pintype "passive"))
    )
    (net (code "140") (name "unconnected-(MD3_2560E-S-Pad5)") (class "Default")
      (node (ref "MD3_2560") (pin "5") (pinfunction "S_5") (pintype "passive"))
    )
    (net (code "141") (name "unconnected-(MD4_2560D-S-Pad4)") (class "Default")
      (node (ref "MD4_2560") (pin "4") (pinfunction "S_4") (pintype "passive"))
    )
    (net (code "142") (name "unconnected-(MD4_2560E-S-Pad5)") (class "Default")
      (node (ref "MD4_2560") (pin "5") (pinfunction "S_5") (pintype "passive"))
    )
    (net (code "143") (name "unconnected-(MD5_2560D-S-Pad4)") (class "Default")
      (node (ref "MD5_2560") (pin "4") (pinfunction "S_4") (pintype "passive"))
    )
    (net (code "144") (name "unconnected-(MD5_2560E-S-Pad5)") (class "Default")
      (node (ref "MD5_2560") (pin "5") (pinfunction "S_5") (pintype "passive"))
    )
    (net (code "145") (name "unconnected-(MD6_2560D-S-Pad4)") (class "Default")
      (node (ref "MD6_2560") (pin "4") (pinfunction "S_4") (pintype "passive"))
    )
    (net (code "146") (name "unconnected-(MD6_2560E-S-Pad5)") (class "Default")
      (node (ref "MD6_2560") (pin "5") (pinfunction "S_5") (pintype "passive"))
    )
    (net (code "147") (name "unconnected-(MD7_2560D-S-Pad4)") (class "Default")
      (node (ref "MD7_2560") (pin "4") (pinfunction "S_4") (pintype "passive"))
    )
    (net (code "148") (name "unconnected-(MD7_2560E-S-Pad5)") (class "Default")
      (node (ref "MD7_2560") (pin "5") (pinfunction "S_5") (pintype "passive"))
    )
    (net (code "149") (name "unconnected-(MD8_2560D-S-Pad4)") (class "Default")
      (node (ref "MD8_2560") (pin "4") (pinfunction "S_4") (pintype "passive"))
    )
    (net (code "150") (name "unconnected-(MD8_2560E-S-Pad5)") (class "Default")
      (node (ref "MD8_2560") (pin "5") (pinfunction "S_5") (pintype "passive"))
    )
    (net (code "151") (name "unconnected-(PS2C-S-Pad3)") (class "Default")
      (node (ref "PS2") (pin "3") (pinfunction "S_3") (pintype "passive"))
    )
    (net (code "152") (name "unconnected-(PS2H-S-Pad8)") (class "Default")
      (node (ref "PS2") (pin "8") (pinfunction "S_8") (pintype "passive"))
    )
    (net (code "153") (name "unconnected-(PS2I-S-Pad9)") (class "Default")
      (node (ref "PS2") (pin "9") (pinfunction "S_9") (pintype "passive"))
    )
  )
)
